# STM32L431RCT6.net
KiCad netlist of a schematic drawn in Altium Designer
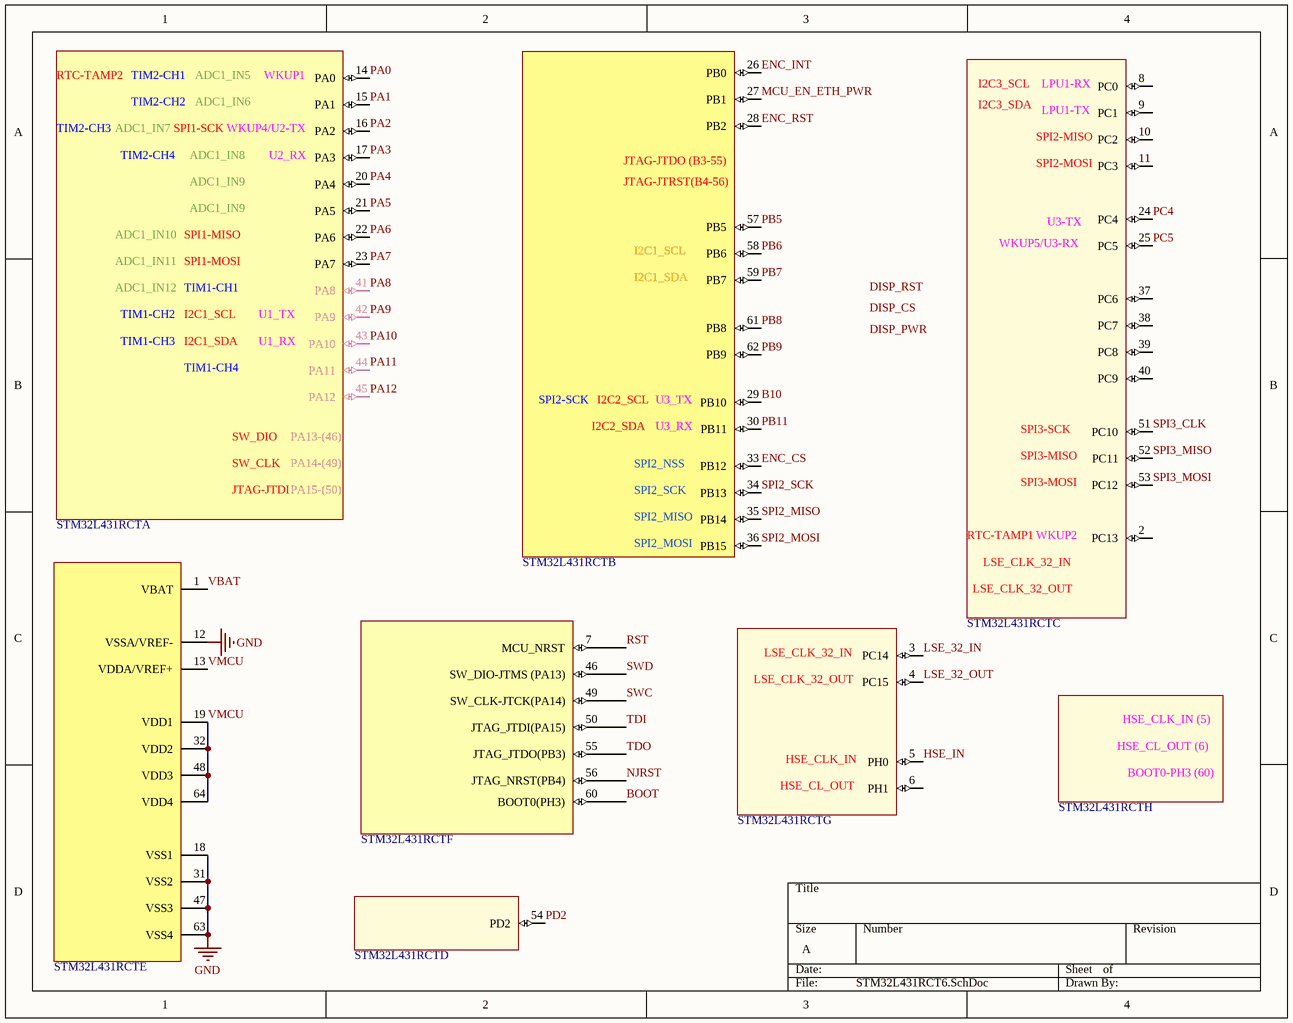
[diagram p0: STM32L431RCT6.SchDoc]

(export (version "E")
  (design (tool "Eeschema 10.0.6"))
  (components
    (comp (ref "STM32L431RCT")
      (value "STM32L431RCT")
      (footprint "STM32l431RCT6_3d")
      (libsource (lib "abr_mcu_st") (part "STM32L431RCT"))
    )
  )
  (nets
    (net (code "1") (name "/B10") (class "Default")
      (node (ref "STM32L431RCT") (pin "29") (pinfunction "PB10_29") (pintype "bidirectional"))
    )
    (net (code "2") (name "/BOOT") (class "Default")
      (node (ref "STM32L431RCT") (pin "60") (pinfunction "BOOT0(PH3)_60") (pintype "bidirectional"))
    )
    (net (code "6") (name "/ENC_CS") (class "Default")
      (node (ref "STM32L431RCT") (pin "33") (pinfunction "PB12_33") (pintype "bidirectional"))
    )
    (net (code "7") (name "/ENC_INT") (class "Default")
      (node (ref "STM32L431RCT") (pin "26") (pinfunction "PB0_26") (pintype "bidirectional"))
    )
    (net (code "8") (name "/ENC_RST") (class "Default")
      (node (ref "STM32L431RCT") (pin "28") (pinfunction "PB2_28") (pintype "bidirectional"))
    )
    (net (code "9") (name "/HSE_IN") (class "Default")
      (node (ref "STM32L431RCT") (pin "5") (pinfunction "PH0_5") (pintype "bidirectional"))
    )
    (net (code "10") (name "/LSE_32_IN") (class "Default")
      (node (ref "STM32L431RCT") (pin "3") (pinfunction "PC14_3") (pintype "bidirectional"))
    )
    (net (code "11") (name "/LSE_32_OUT") (class "Default")
      (node (ref "STM32L431RCT") (pin "4") (pinfunction "PC15_4") (pintype "bidirectional"))
    )
    (net (code "12") (name "/MCU_EN_ETH_PWR") (class "Default")
      (node (ref "STM32L431RCT") (pin "27") (pinfunction "PB1_27") (pintype "bidirectional"))
    )
    (net (code "13") (name "/NJRST") (class "Default")
      (node (ref "STM32L431RCT") (pin "56") (pinfunction "JTAG_NRST(PB4)_56") (pintype "bidirectional"))
    )
    (net (code "14") (name "/PA0") (class "Default")
      (node (ref "STM32L431RCT") (pin "14") (pinfunction "PA0_14") (pintype "bidirectional"))
    )
    (net (code "15") (name "/PA1") (class "Default")
      (node (ref "STM32L431RCT") (pin "15") (pinfunction "PA1_15") (pintype "bidirectional"))
    )
    (net (code "16") (name "/PA2") (class "Default")
      (node (ref "STM32L431RCT") (pin "16") (pinfunction "PA2_16") (pintype "bidirectional"))
    )
    (net (code "17") (name "/PA3") (class "Default")
      (node (ref "STM32L431RCT") (pin "17") (pinfunction "PA3_17") (pintype "bidirectional"))
    )
    (net (code "18") (name "/PA4") (class "Default")
      (node (ref "STM32L431RCT") (pin "20") (pinfunction "PA4_20") (pintype "bidirectional"))
    )
    (net (code "19") (name "/PA5") (class "Default")
      (node (ref "STM32L431RCT") (pin "21") (pinfunction "PA5_21") (pintype "bidirectional"))
    )
    (net (code "20") (name "/PA6") (class "Default")
      (node (ref "STM32L431RCT") (pin "22") (pinfunction "PA6_22") (pintype "bidirectional"))
    )
    (net (code "21") (name "/PA7") (class "Default")
      (node (ref "STM32L431RCT") (pin "23") (pinfunction "PA7_23") (pintype "bidirectional"))
    )
    (net (code "22") (name "/PA8") (class "Default")
      (node (ref "STM32L431RCT") (pin "41") (pinfunction "PA8_41") (pintype "bidirectional"))
    )
    (net (code "23") (name "/PA9") (class "Default")
      (node (ref "STM32L431RCT") (pin "42") (pinfunction "PA9_42") (pintype "bidirectional"))
    )
    (net (code "24") (name "/PA10") (class "Default")
      (node (ref "STM32L431RCT") (pin "43") (pinfunction "PA10_43") (pintype "bidirectional"))
    )
    (net (code "26") (name "/PA11") (class "Default")
      (node (ref "STM32L431RCT") (pin "44") (pinfunction "PA11_44") (pintype "bidirectional"))
    )
    (net (code "27") (name "/PA12") (class "Default")
      (node (ref "STM32L431RCT") (pin "45") (pinfunction "PA12_45") (pintype "bidirectional"))
    )
    (net (code "28") (name "/PB5") (class "Default")
      (node (ref "STM32L431RCT") (pin "57") (pinfunction "PB5_57") (pintype "bidirectional"))
    )
    (net (code "29") (name "/PB6") (class "Default")
      (node (ref "STM32L431RCT") (pin "58") (pinfunction "PB6_58") (pintype "bidirectional"))
    )
    (net (code "30") (name "/PB7") (class "Default")
      (node (ref "STM32L431RCT") (pin "59") (pinfunction "PB7_59") (pintype "bidirectional"))
    )
    (net (code "31") (name "/PB8") (class "Default")
      (node (ref "STM32L431RCT") (pin "61") (pinfunction "PB8_61") (pintype "bidirectional"))
    )
    (net (code "32") (name "/PB9") (class "Default")
      (node (ref "STM32L431RCT") (pin "62") (pinfunction "PB9_62") (pintype "bidirectional"))
    )
    (net (code "33") (name "/PB11") (class "Default")
      (node (ref "STM32L431RCT") (pin "30") (pinfunction "PB11_30") (pintype "bidirectional"))
    )
    (net (code "34") (name "/PC4") (class "Default")
      (node (ref "STM32L431RCT") (pin "24") (pinfunction "PC4_24") (pintype "bidirectional"))
    )
    (net (code "35") (name "/PC5") (class "Default")
      (node (ref "STM32L431RCT") (pin "25") (pinfunction "PC5_25") (pintype "bidirectional"))
    )
    (net (code "36") (name "/PD2") (class "Default")
      (node (ref "STM32L431RCT") (pin "54") (pinfunction "PD2_54") (pintype "bidirectional"))
    )
    (net (code "37") (name "/RST") (class "Default")
      (node (ref "STM32L431RCT") (pin "7") (pinfunction "MCU_NRST_7") (pintype "bidirectional"))
    )
    (net (code "38") (name "/SPI2_MISO") (class "Default")
      (node (ref "STM32L431RCT") (pin "35") (pinfunction "PB14_35") (pintype "bidirectional"))
    )
    (net (code "39") (name "/SPI2_MOSI") (class "Default")
      (node (ref "STM32L431RCT") (pin "36") (pinfunction "PB15_36") (pintype "bidirectional"))
    )
    (net (code "40") (name "/SPI2_SCK") (class "Default")
      (node (ref "STM32L431RCT") (pin "34") (pinfunction "PB13_34") (pintype "bidirectional"))
    )
    (net (code "41") (name "/SPI3_CLK") (class "Default")
      (node (ref "STM32L431RCT") (pin "51") (pinfunction "PC10_51") (pintype "bidirectional"))
    )
    (net (code "42") (name "/SPI3_MISO") (class "Default")
      (node (ref "STM32L431RCT") (pin "52") (pinfunction "PC11_52") (pintype "bidirectional"))
    )
    (net (code "43") (name "/SPI3_MOSI") (class "Default")
      (node (ref "STM32L431RCT") (pin "53") (pinfunction "PC12_53") (pintype "bidirectional"))
    )
    (net (code "44") (name "/SWC") (class "Default")
      (node (ref "STM32L431RCT") (pin "49") (pinfunction "SW_CLK-JTCK(PA14)_49") (pintype "bidirectional"))
    )
    (net (code "45") (name "/SWD") (class "Default")
      (node (ref "STM32L431RCT") (pin "46") (pinfunction "SW_DIO-JTMS_(PA13)_46") (pintype "bidirectional"))
    )
    (net (code "46") (name "/TDI") (class "Default")
      (node (ref "STM32L431RCT") (pin "50") (pinfunction "JTAG_JTDI(PA15)_50") (pintype "bidirectional"))
    )
    (net (code "47") (name "/TDO") (class "Default")
      (node (ref "STM32L431RCT") (pin "55") (pinfunction "JTAG_JTDO(PB3)_55") (pintype "bidirectional"))
    )
    (net (code "48") (name "/VBAT") (class "Default")
      (node (ref "STM32L431RCT") (pin "1") (pinfunction "VBAT_1") (pintype "power_in"))
    )
    (net (code "49") (name "/VMCU") (class "Default")
      (node (ref "STM32L431RCT") (pin "13") (pinfunction "VDDA/VREF+_13") (pintype "power_in"))
      (node (ref "STM32L431RCT") (pin "19") (pinfunction "VDD1_19") (pintype "power_in"))
      (node (ref "STM32L431RCT") (pin "32") (pinfunction "VDD2_32") (pintype "power_in"))
      (node (ref "STM32L431RCT") (pin "48") (pinfunction "VDD3_48") (pintype "power_in"))
      (node (ref "STM32L431RCT") (pin "64") (pinfunction "VDD4_64") (pintype "power_in"))
    )
    (net (code "50") (name "GND") (class "Default")
      (node (ref "STM32L431RCT") (pin "12") (pinfunction "VSSA/VREF-_12") (pintype "power_in"))
      (node (ref "STM32L431RCT") (pin "18") (pinfunction "VSS1_18") (pintype "power_in"))
      (node (ref "STM32L431RCT") (pin "31") (pinfunction "VSS2_31") (pintype "power_in"))
      (node (ref "STM32L431RCT") (pin "47") (pinfunction "VSS3_47") (pintype "power_in"))
      (node (ref "STM32L431RCT") (pin "63") (pinfunction "VSS4_63") (pintype "power_in"))
    )
    (net (code "51") (name "unconnected-(STM32L431RCTC-PC0-Pad8)") (class "Default")
      (node (ref "STM32L431RCT") (pin "8") (pinfunction "PC0_8") (pintype "bidirectional"))
    )
    (net (code "52") (name "unconnected-(STM32L431RCTC-PC1-Pad9)") (class "Default")
      (node (ref "STM32L431RCT") (pin "9") (pinfunction "PC1_9") (pintype "bidirectional"))
    )
    (net (code "53") (name "unconnected-(STM32L431RCTC-PC2-Pad10)") (class "Default")
      (node (ref "STM32L431RCT") (pin "10") (pinfunction "PC2_10") (pintype "bidirectional"))
    )
    (net (code "54") (name "unconnected-(STM32L431RCTC-PC3-Pad11)") (class "Default")
      (node (ref "STM32L431RCT") (pin "11") (pinfunction "PC3_11") (pintype "bidirectional"))
    )
    (net (code "55") (name "unconnected-(STM32L431RCTC-PC6-Pad37)") (class "Default")
      (node (ref "STM32L431RCT") (pin "37") (pinfunction "PC6_37") (pintype "bidirectional"))
    )
    (net (code "56") (name "unconnected-(STM32L431RCTC-PC7-Pad38)") (class "Default")
      (node (ref "STM32L431RCT") (pin "38") (pinfunction "PC7_38") (pintype "bidirectional"))
    )
    (net (code "57") (name "unconnected-(STM32L431RCTC-PC8-Pad39)") (class "Default")
      (node (ref "STM32L431RCT") (pin "39") (pinfunction "PC8_39") (pintype "bidirectional"))
    )
    (net (code "58") (name "unconnected-(STM32L431RCTC-PC9-Pad40)") (class "Default")
      (node (ref "STM32L431RCT") (pin "40") (pinfunction "PC9_40") (pintype "bidirectional"))
    )
    (net (code "59") (name "unconnected-(STM32L431RCTC-PC13-Pad2)") (class "Default")
      (node (ref "STM32L431RCT") (pin "2") (pinfunction "PC13_2") (pintype "bidirectional"))
    )
    (net (code "60") (name "unconnected-(STM32L431RCTG-PH1-Pad6)") (class "Default")
      (node (ref "STM32L431RCT") (pin "6") (pinfunction "PH1_6") (pintype "bidirectional"))
    )
  )
)
